# f6_Pluse.net
KiCad netlist of a schematic drawn in EAGLE
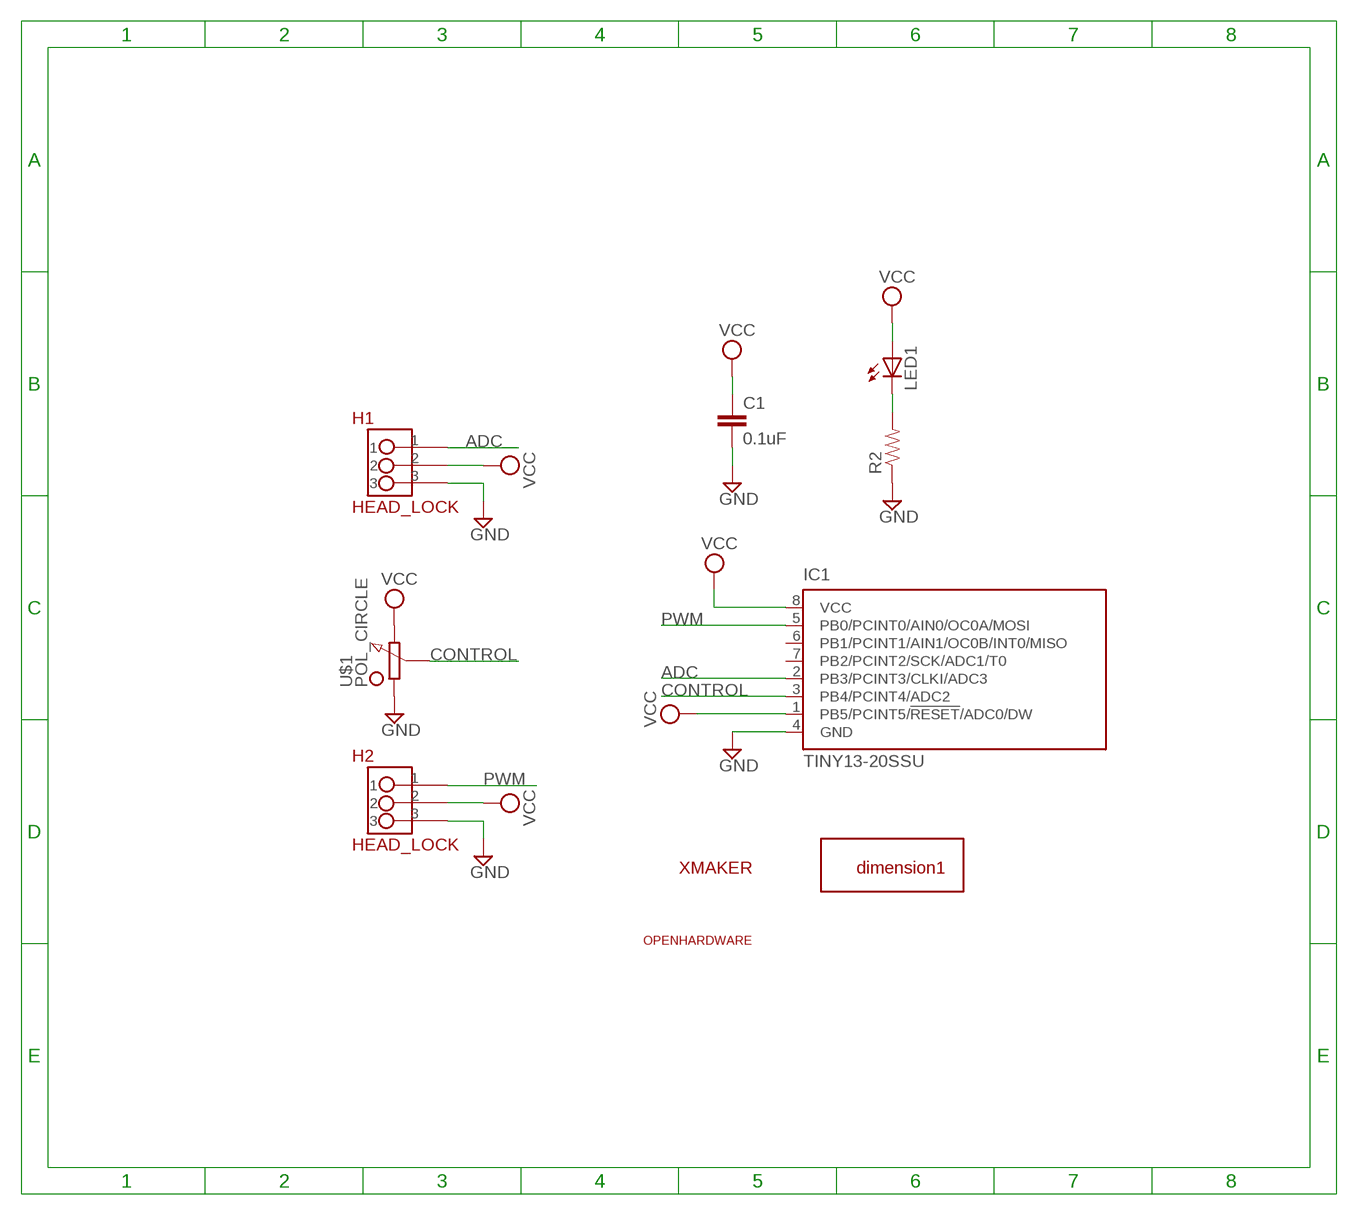
[diagram p0: schematic, sheet 1]

(export (version "E")
  (design (tool "Eeschema 10.0.6"))
  (components
    (comp (ref "C1")
      (value "0.1uF")
      (footprint "eagle-import:0603-CAP")
      (libsource (lib "eagle-import") (part "CAP0603-CAP"))
    )
    (comp (ref "H1")
      (value "HEAD_LOCK")
      (footprint "eagle-import:HEAD_LOCK")
      (libsource (lib "eagle-import") (part "HEAD_LOCK"))
    )
    (comp (ref "H2")
      (value "HEAD_LOCK")
      (footprint "eagle-import:HEAD_LOCK")
      (libsource (lib "eagle-import") (part "HEAD_LOCK"))
    )
    (comp (ref "IC1")
      (value "TINY13-20SSU")
      (footprint "eagle-import:8S1")
      (fields (field (name "MPN") "ATTINY13-20SSU"))
      (libsource (lib "eagle-import") (part "TINY13SSU-20"))
    )
    (comp (ref "LED1")
      (value "LED_ESML0603")
      (footprint "eagle-import:LED_SML0603")
      (libsource (lib "eagle-import") (part "LED_ESML0603"))
    )
    (comp (ref "R2")
      (value "0.27OHM-1/10W-1%(0603)")
      (footprint "eagle-import:0603-RES")
      (libsource (lib "eagle-import") (part "0.27OHM-1/10W-1%(0603)"))
    )
    (comp (ref "U$1")
      (value "POL_CIRCLE")
      (footprint "eagle-import:POT_CIRCLE")
      (libsource (lib "eagle-import") (part "POL_CIRCLE"))
    )
    (comp (ref "U$2")
      (value "XMAKERLOGO2")
      (footprint "eagle-import:XMAKERLOGO2")
      (libsource (lib "eagle-import") (part "XMAKERLOGO2"))
    )
    (comp (ref "U$3")
      (value "DIMENSION1")
      (footprint "eagle-import:DIMENSION1")
      (libsource (lib "eagle-import") (part "DIMENSION1"))
    )
    (comp (ref "U$4")
      (value "OPENHARDWARE")
      (footprint "eagle-import:OPENHARDWARE")
      (libsource (lib "eagle-import") (part "OPENHARDWARE"))
    )
  )
  (nets
    (net (code "1") (name "/ADC") (class "Default")
      (node (ref "H1") (pin "1") (pinfunction "1_1") (pintype "passive"))
      (node (ref "IC1") (pin "2") (pinfunction "PB3/PCINT3/CLKI/ADC3_2") (pintype "bidirectional"))
    )
    (net (code "2") (name "/CONTROL") (class "Default")
      (node (ref "IC1") (pin "3") (pinfunction "PB4/PCINT4/ADC2_3") (pintype "bidirectional"))
      (node (ref "U$1") (pin "P$2") (pinfunction "2_P$2") (pintype "passive"))
    )
    (net (code "3") (name "/PWM") (class "Default")
      (node (ref "H2") (pin "1") (pinfunction "1_1") (pintype "passive"))
      (node (ref "IC1") (pin "5") (pinfunction "PB0/PCINT0/AIN0/OC0A/MOSI_5") (pintype "bidirectional"))
    )
    (net (code "4") (name "GND") (class "Default")
      (node (ref "C1") (pin "2") (pinfunction "2_2") (pintype "passive"))
      (node (ref "H1") (pin "3") (pinfunction "3_3") (pintype "passive"))
      (node (ref "H2") (pin "3") (pinfunction "3_3") (pintype "passive"))
      (node (ref "IC1") (pin "4") (pinfunction "GND_4") (pintype "power_in"))
      (node (ref "R2") (pin "1") (pinfunction "1_1") (pintype "passive"))
      (node (ref "U$1") (pin "P$3") (pinfunction "3_P$3") (pintype "passive"))
    )
    (net (code "5") (name "Net-(LED1-PadC)") (class "Default")
      (node (ref "LED1") (pin "C") (pinfunction "C_C") (pintype "passive"))
      (node (ref "R2") (pin "2") (pinfunction "2_2") (pintype "passive"))
    )
    (net (code "6") (name "VCC") (class "Default")
      (node (ref "C1") (pin "1") (pinfunction "1_1") (pintype "passive"))
      (node (ref "H1") (pin "2") (pinfunction "2_2") (pintype "passive"))
      (node (ref "H2") (pin "2") (pinfunction "2_2") (pintype "passive"))
      (node (ref "IC1") (pin "1") (pinfunction "PB5/PCINT5/~{RESET}/ADC0/DW_1") (pintype "bidirectional"))
      (node (ref "IC1") (pin "8") (pinfunction "VCC_8") (pintype "power_in"))
      (node (ref "LED1") (pin "A") (pinfunction "A_A") (pintype "passive"))
      (node (ref "U$1") (pin "P$1") (pinfunction "1_P$1") (pintype "passive"))
    )
    (net (code "7") (name "unconnected-(IC1-PB1{slash}PCINT1{slash}AIN1{slash}OC0B{slash}INT0{slash}MISO-Pad6)") (class "Default")
      (node (ref "IC1") (pin "6") (pinfunction "PB1/PCINT1/AIN1/OC0B/INT0/MISO_6") (pintype "bidirectional"))
    )
    (net (code "8") (name "unconnected-(IC1-PB2{slash}PCINT2{slash}SCK{slash}ADC1{slash}T0-Pad7)") (class "Default")
      (node (ref "IC1") (pin "7") (pinfunction "PB2/PCINT2/SCK/ADC1/T0_7") (pintype "bidirectional"))
    )
  )
)
